# ISD1730.net
KiCad netlist of a schematic drawn in Altium Designer
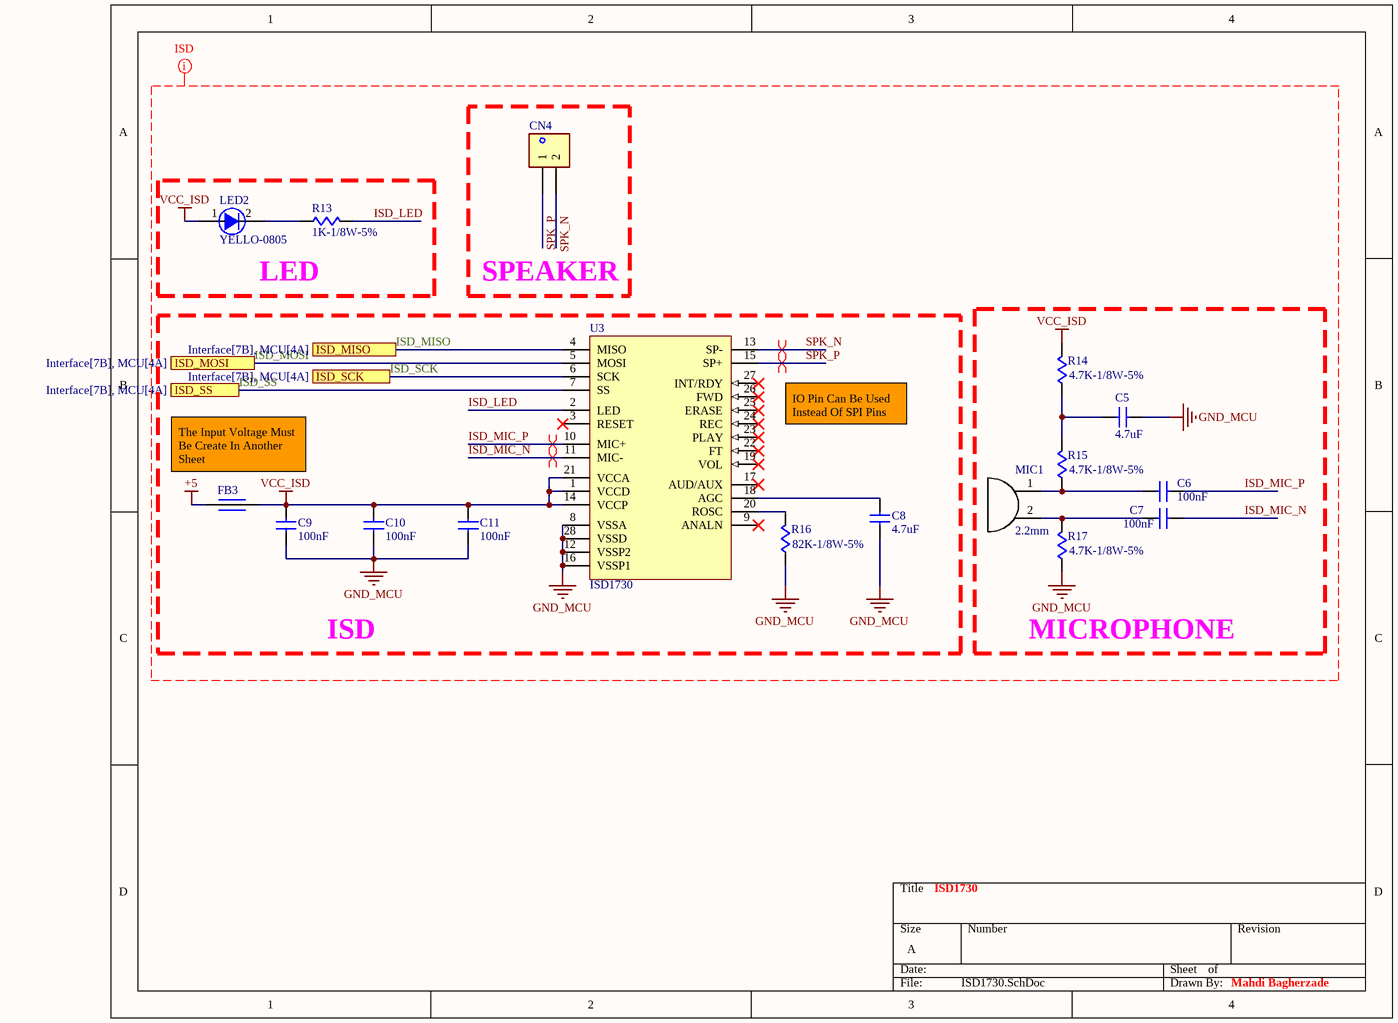
[diagram p0: ISD1730.SchDoc]

(export (version "E")
  (design (tool "Eeschema 10.0.6"))
  (components
    (comp (ref "C5")
      (value "4.7uF")
      (footprint "C-0805")
      (description "CAPACITOR")
      (fields
        (field (name "VOLTAGE") "50V")
        (field (name "TOLERANCE") "X7R")
        (field (name "PUBLISHER") "Mahdi Bagherzadeh")
      )
      (libsource (lib "Mahdi-Bagherzadeh") (part "CAP-CER"))
    )
    (comp (ref "C6")
      (value "100nF")
      (footprint "C-0805")
      (description "CAPACITOR")
      (fields
        (field (name "VOLTAGE") "50V")
        (field (name "TOLERANCE") "X7R")
        (field (name "PUBLISHER") "Mahdi Bagherzadeh")
      )
      (libsource (lib "Mahdi-Bagherzadeh") (part "CAP-CER"))
    )
    (comp (ref "C7")
      (value "100nF")
      (footprint "C-0805")
      (description "CAPACITOR")
      (fields
        (field (name "VOLTAGE") "50V")
        (field (name "TOLERANCE") "X7R")
        (field (name "PUBLISHER") "Mahdi Bagherzadeh")
      )
      (libsource (lib "Mahdi-Bagherzadeh") (part "CAP-CER"))
    )
    (comp (ref "C8")
      (value "4.7uF")
      (footprint "C-0805")
      (description "CAPACITOR")
      (fields
        (field (name "VOLTAGE") "50V")
        (field (name "TOLERANCE") "X7R")
        (field (name "PUBLISHER") "Mahdi Bagherzadeh")
      )
      (libsource (lib "Mahdi-Bagherzadeh") (part "CAP-CER"))
    )
    (comp (ref "C9")
      (value "100nF")
      (footprint "C-0805")
      (description "CAPACITOR")
      (fields
        (field (name "VOLTAGE") "50V")
        (field (name "TOLERANCE") "X7R")
        (field (name "PUBLISHER") "Mahdi Bagherzadeh")
      )
      (libsource (lib "Mahdi-Bagherzadeh") (part "CAP-CER"))
    )
    (comp (ref "C10")
      (value "100nF")
      (footprint "C-0805")
      (description "CAPACITOR")
      (fields
        (field (name "VOLTAGE") "50V")
        (field (name "TOLERANCE") "X7R")
        (field (name "PUBLISHER") "Mahdi Bagherzadeh")
      )
      (libsource (lib "Mahdi-Bagherzadeh") (part "CAP-CER"))
    )
    (comp (ref "C11")
      (value "100nF")
      (footprint "C-0805")
      (description "CAPACITOR")
      (fields
        (field (name "VOLTAGE") "50V")
        (field (name "TOLERANCE") "X7R")
        (field (name "PUBLISHER") "Mahdi Bagherzadeh")
      )
      (libsource (lib "Mahdi-Bagherzadeh") (part "CAP-CER"))
    )
    (comp (ref "CN4")
      (value "XH-2")
      (footprint "XH-2")
      (description "CONNECTOR")
      (fields (field (name "PUBLISHER") "Mahdi Bagherzadeh"))
      (libsource (lib "Mahdi-Bagherzadeh") (part "CN-2pin"))
    )
    (comp (ref "FB3")
      (value "FERRITE BEAD")
      (footprint "FB-0805")
      (description "INDUCATOR")
      (fields (field (name "PUBLISHER") "Mahdi Bagherzadeh"))
      (libsource (lib "Mahdi-Bagherzadeh") (part "FERRITE BEAD"))
    )
    (comp (ref "LED2")
      (value "YELLO-0805")
      (footprint "LED-1206-G")
      (description "LED")
      (fields (field (name "PUBLISHER") "Mahdi Bagherzadeh"))
      (libsource (lib "Mahdi-Bagherzadeh") (part "LED"))
    )
    (comp (ref "MIC1")
      (value "2.2mm")
      (footprint "MIC-2.2mm")
      (description "MIC")
      (fields (field (name "PUBLISHER") "Mahdi Bagherzadeh"))
      (libsource (lib "Mahdi-Bagherzadeh") (part "MIC"))
    )
    (comp (ref "R13")
      (value "1K-1/8W-5%")
      (footprint "R-0805")
      (description "RESISTOR")
      (fields (field (name "PUBLISHER") "Mahdi Bagherzadeh"))
      (libsource (lib "Mahdi-Bagherzadeh") (part "RES"))
    )
    (comp (ref "R14")
      (value "4.7K-1/8W-5%")
      (footprint "R-0805")
      (description "RESISTOR")
      (fields (field (name "PUBLISHER") "Mahdi Bagherzadeh"))
      (libsource (lib "Mahdi-Bagherzadeh") (part "RES"))
    )
    (comp (ref "R15")
      (value "4.7K-1/8W-5%")
      (footprint "R-0805")
      (description "RESISTOR")
      (fields (field (name "PUBLISHER") "Mahdi Bagherzadeh"))
      (libsource (lib "Mahdi-Bagherzadeh") (part "RES"))
    )
    (comp (ref "R16")
      (value "82K-1/8W-5%")
      (footprint "R-0805")
      (description "RESISTOR")
      (fields (field (name "PUBLISHER") "Mahdi Bagherzadeh"))
      (libsource (lib "Mahdi-Bagherzadeh") (part "RES"))
    )
    (comp (ref "R17")
      (value "4.7K-1/8W-5%")
      (footprint "R-0805")
      (description "RESISTOR")
      (fields (field (name "PUBLISHER") "Mahdi Bagherzadeh"))
      (libsource (lib "Mahdi-Bagherzadeh") (part "RES"))
    )
    (comp (ref "U3")
      (value "ISD1730")
      (footprint "DIP28-wide")
      (description "IC")
      (fields (field (name "PUBLISHER") "Mahdi Bagherzadeh"))
      (libsource (lib "Mahdi-Bagherzadeh") (part "ISD1730"))
    )
  )
  (nets
    (net (code "1") (name "+5") (class "Default")
      (node (ref "FB3") (pin "1") (pinfunction "1_1") (pintype "passive"))
    )
    (net (code "2") (name "/ISD_LED") (class "Default")
      (node (ref "R13") (pin "2") (pinfunction "2_2") (pintype "passive"))
      (node (ref "U3") (pin "2") (pinfunction "LED_2") (pintype "passive"))
    )
    (net (code "3") (name "/ISD_MIC_N") (class "Default")
      (node (ref "C7") (pin "2") (pinfunction "2_2") (pintype "passive"))
      (node (ref "U3") (pin "11") (pinfunction "MIC-_11") (pintype "passive"))
    )
    (net (code "4") (name "/ISD_MIC_P") (class "Default")
      (node (ref "C6") (pin "2") (pinfunction "2_2") (pintype "passive"))
      (node (ref "U3") (pin "10") (pinfunction "MIC+_10") (pintype "passive"))
    )
    (net (code "5") (name "/ISD_MISO") (class "Default")
      (node (ref "U3") (pin "4") (pinfunction "MISO_4") (pintype "passive"))
    )
    (net (code "6") (name "/ISD_MOSI") (class "Default")
      (node (ref "U3") (pin "5") (pinfunction "MOSI_5") (pintype "passive"))
    )
    (net (code "7") (name "/ISD_SCK") (class "Default")
      (node (ref "U3") (pin "6") (pinfunction "SCK_6") (pintype "passive"))
    )
    (net (code "8") (name "/ISD_SS") (class "Default")
      (node (ref "U3") (pin "7") (pinfunction "SS_7") (pintype "passive"))
    )
    (net (code "9") (name "/SPK_N") (class "Default")
      (node (ref "CN4") (pin "2") (pinfunction "2_2") (pintype "passive"))
      (node (ref "U3") (pin "13") (pinfunction "SP-_13") (pintype "passive"))
    )
    (net (code "10") (name "/SPK_P") (class "Default")
      (node (ref "CN4") (pin "1") (pinfunction "1_1") (pintype "passive"))
      (node (ref "U3") (pin "15") (pinfunction "SP+_15") (pintype "passive"))
    )
    (net (code "11") (name "GND_MCU") (class "Default")
      (node (ref "C10") (pin "2") (pinfunction "2_2") (pintype "passive"))
      (node (ref "C11") (pin "2") (pinfunction "2_2") (pintype "passive"))
      (node (ref "C5") (pin "2") (pinfunction "2_2") (pintype "passive"))
      (node (ref "C8") (pin "2") (pinfunction "2_2") (pintype "passive"))
      (node (ref "C9") (pin "2") (pinfunction "2_2") (pintype "passive"))
      (node (ref "R16") (pin "1") (pinfunction "1_1") (pintype "passive"))
      (node (ref "R17") (pin "1") (pinfunction "1_1") (pintype "passive"))
      (node (ref "U3") (pin "12") (pinfunction "VSSP2_12") (pintype "power_in"))
      (node (ref "U3") (pin "16") (pinfunction "VSSP1_16") (pintype "power_in"))
      (node (ref "U3") (pin "28") (pinfunction "VSSD_28") (pintype "power_in"))
      (node (ref "U3") (pin "8") (pinfunction "VSSA_8") (pintype "power_in"))
    )
    (net (code "12") (name "Net-(C5-Pad1)") (class "Default")
      (node (ref "C5") (pin "1") (pinfunction "1_1") (pintype "passive"))
      (node (ref "R14") (pin "1") (pinfunction "1_1") (pintype "passive"))
      (node (ref "R15") (pin "2") (pinfunction "2_2") (pintype "passive"))
    )
    (net (code "13") (name "Net-(C6-Pad1)") (class "Default")
      (node (ref "C6") (pin "1") (pinfunction "1_1") (pintype "passive"))
      (node (ref "MIC1") (pin "1") (pinfunction "1_1") (pintype "passive"))
      (node (ref "R15") (pin "1") (pinfunction "1_1") (pintype "passive"))
    )
    (net (code "14") (name "Net-(C7-Pad1)") (class "Default")
      (node (ref "C7") (pin "1") (pinfunction "1_1") (pintype "passive"))
      (node (ref "MIC1") (pin "2") (pinfunction "2_2") (pintype "passive"))
      (node (ref "R17") (pin "2") (pinfunction "2_2") (pintype "passive"))
    )
    (net (code "15") (name "Net-(LED2-C)") (class "Default")
      (node (ref "LED2") (pin "2") (pinfunction "C_2") (pintype "passive"))
      (node (ref "R13") (pin "1") (pinfunction "1_1") (pintype "passive"))
    )
    (net (code "16") (name "Net-(U3-AGC)") (class "Default")
      (node (ref "C8") (pin "1") (pinfunction "1_1") (pintype "passive"))
      (node (ref "U3") (pin "18") (pinfunction "AGC_18") (pintype "passive"))
    )
    (net (code "17") (name "Net-(U3-ROSC)") (class "Default")
      (node (ref "R16") (pin "2") (pinfunction "2_2") (pintype "passive"))
      (node (ref "U3") (pin "20") (pinfunction "ROSC_20") (pintype "passive"))
    )
    (net (code "18") (name "VCC_ISD") (class "Default")
      (node (ref "C10") (pin "1") (pinfunction "1_1") (pintype "passive"))
      (node (ref "C11") (pin "1") (pinfunction "1_1") (pintype "passive"))
      (node (ref "C9") (pin "1") (pinfunction "1_1") (pintype "passive"))
      (node (ref "FB3") (pin "2") (pinfunction "2_2") (pintype "passive"))
      (node (ref "LED2") (pin "1") (pinfunction "A_1") (pintype "passive"))
      (node (ref "R14") (pin "2") (pinfunction "2_2") (pintype "passive"))
      (node (ref "U3") (pin "1") (pinfunction "VCCD_1") (pintype "power_in"))
      (node (ref "U3") (pin "14") (pinfunction "VCCP_14") (pintype "power_in"))
      (node (ref "U3") (pin "21") (pinfunction "VCCA_21") (pintype "power_in"))
    )
    (net (code "19") (name "unconnected-(U3-ANALN-Pad9)") (class "Default")
      (node (ref "U3") (pin "9") (pinfunction "ANALN_9") (pintype "passive+no_connect"))
    )
    (net (code "20") (name "unconnected-(U3-AUD{slash}AUX-Pad17)") (class "Default")
      (node (ref "U3") (pin "17") (pinfunction "AUD/AUX_17") (pintype "passive+no_connect"))
    )
    (net (code "21") (name "unconnected-(U3-ERASE-Pad25)") (class "Default")
      (node (ref "U3") (pin "25") (pinfunction "ERASE_25") (pintype "input+no_connect"))
    )
    (net (code "22") (name "unconnected-(U3-FT-Pad22)") (class "Default")
      (node (ref "U3") (pin "22") (pinfunction "FT_22") (pintype "input+no_connect"))
    )
    (net (code "23") (name "unconnected-(U3-FWD-Pad26)") (class "Default")
      (node (ref "U3") (pin "26") (pinfunction "FWD_26") (pintype "input+no_connect"))
    )
    (net (code "24") (name "unconnected-(U3-INT{slash}RDY-Pad27)") (class "Default")
      (node (ref "U3") (pin "27") (pinfunction "INT/RDY_27") (pintype "input+no_connect"))
    )
    (net (code "25") (name "unconnected-(U3-PLAY-Pad23)") (class "Default")
      (node (ref "U3") (pin "23") (pinfunction "PLAY_23") (pintype "input+no_connect"))
    )
    (net (code "26") (name "unconnected-(U3-REC-Pad24)") (class "Default")
      (node (ref "U3") (pin "24") (pinfunction "REC_24") (pintype "input+no_connect"))
    )
    (net (code "27") (name "unconnected-(U3-RESET-Pad3)") (class "Default")
      (node (ref "U3") (pin "3") (pinfunction "RESET_3") (pintype "passive+no_connect"))
    )
    (net (code "28") (name "unconnected-(U3-VOL-Pad19)") (class "Default")
      (node (ref "U3") (pin "19") (pinfunction "VOL_19") (pintype "input+no_connect"))
    )
  )
)
